# rpi_shield.net
KiCad netlist of a schematic drawn in Altium Designer
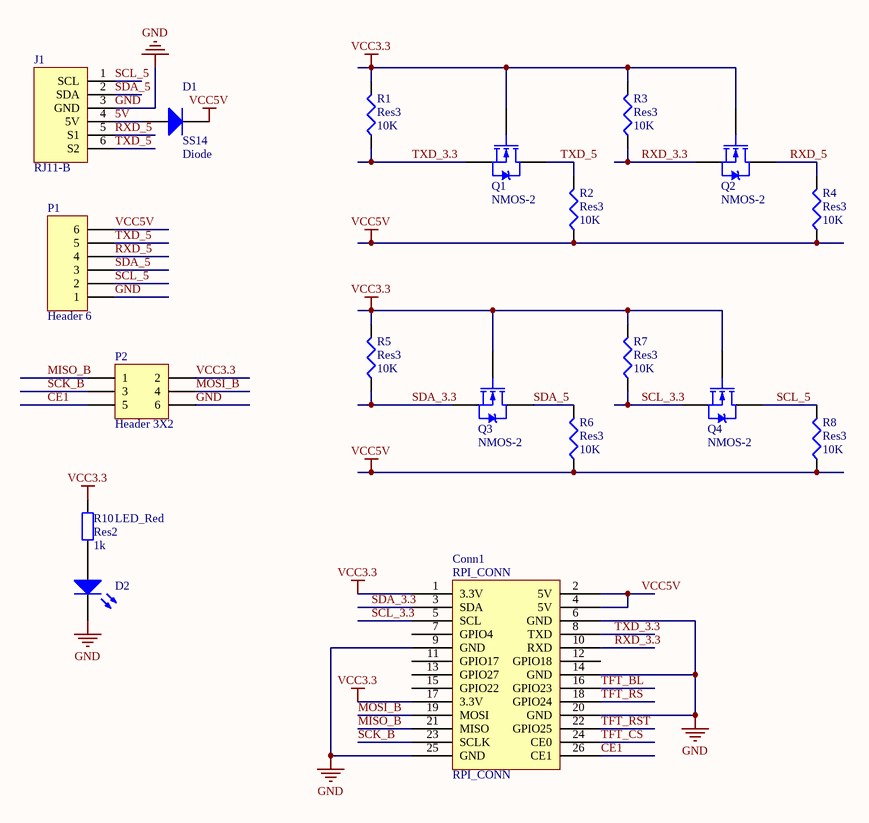
[diagram p0: rpi_shield.SchDoc]

(export (version "E")
  (design (tool "Eeschema 10.0.6"))
  (components
    (comp (ref "Conn1") (value "RPI_CONN") (footprint "HDR2X13") (libsource (lib "rpi") (part "RPI_CONN")))
    (comp (ref "D1")
      (value "Diode")
      (footprint "DO-214")
      (description "Default Diode")
      (fields (field (name "ALTIUM_VALUE") "SS14") (field (name "PUBLISHER") "Altium Limited"))
      (libsource (lib "Miscellaneous Devices") (part "Diode"))
    )
    (comp (ref "D2")
      (value "LED_Red")
      (footprint "D0603_B")
      (description "Typical BLUE SiC LED")
      (fields (field (name "PUBLISHER") "Altium Limited"))
      (libsource (lib "Miscellaneous Devices") (part "LED3"))
    )
    (comp (ref "J1") (value "RJ11-B") (footprint "PCB-606") (libsource (lib "Mylib") (part "RJ11-B")))
    (comp (ref "P1")
      (value "Header 6")
      (footprint "HDR1X6")
      (description "Header, 6-Pin")
      (fields (field (name "PUBLISHER") "Altium Limited"))
      (libsource (lib "Miscellaneous Connectors") (part "Header 6"))
    )
    (comp (ref "P2")
      (value "Header 3X2")
      (footprint "HDR2X3")
      (description "Header, 3-Pin, Dual row")
      (fields (field (name "PUBLISHER") "Altium Limited"))
      (libsource (lib "Miscellaneous Connectors") (part "Header 3X2"))
    )
    (comp (ref "Q1")
      (value "NMOS-2")
      (footprint "SOT-23-3")
      (description "N-Channel Power MOSFET")
      (fields (field (name "PUBLISHER") "Altium Limited"))
      (libsource (lib "Miscellaneous Devices") (part "NMOS-2"))
    )
    (comp (ref "Q2")
      (value "NMOS-2")
      (footprint "SOT-23-3")
      (description "N-Channel Power MOSFET")
      (fields (field (name "PUBLISHER") "Altium Limited"))
      (libsource (lib "Miscellaneous Devices") (part "NMOS-2"))
    )
    (comp (ref "Q3")
      (value "NMOS-2")
      (footprint "SOT-23-3")
      (description "N-Channel Power MOSFET")
      (fields (field (name "PUBLISHER") "Altium Limited"))
      (libsource (lib "Miscellaneous Devices") (part "NMOS-2"))
    )
    (comp (ref "Q4")
      (value "NMOS-2")
      (footprint "SOT-23-3")
      (description "N-Channel Power MOSFET")
      (fields (field (name "PUBLISHER") "Altium Limited"))
      (libsource (lib "Miscellaneous Devices") (part "NMOS-2"))
    )
    (comp (ref "R1")
      (value "Res3")
      (footprint "J1-0603")
      (description "Resistor")
      (fields (field (name "ALTIUM_VALUE") "10K") (field (name "PUBLISHER") "Altium Limited"))
      (libsource (lib "Miscellaneous Devices") (part "Res3"))
    )
    (comp (ref "R2")
      (value "Res3")
      (footprint "J1-0603")
      (description "Resistor")
      (fields (field (name "ALTIUM_VALUE") "10K") (field (name "PUBLISHER") "Altium Limited"))
      (libsource (lib "Miscellaneous Devices") (part "Res3"))
    )
    (comp (ref "R3")
      (value "Res3")
      (footprint "J1-0603")
      (description "Resistor")
      (fields (field (name "ALTIUM_VALUE") "10K") (field (name "PUBLISHER") "Altium Limited"))
      (libsource (lib "Miscellaneous Devices") (part "Res3"))
    )
    (comp (ref "R4")
      (value "Res3")
      (footprint "J1-0603")
      (description "Resistor")
      (fields (field (name "ALTIUM_VALUE") "10K") (field (name "PUBLISHER") "Altium Limited"))
      (libsource (lib "Miscellaneous Devices") (part "Res3"))
    )
    (comp (ref "R5")
      (value "Res3")
      (footprint "J1-0603")
      (description "Resistor")
      (fields (field (name "ALTIUM_VALUE") "10K") (field (name "PUBLISHER") "Altium Limited"))
      (libsource (lib "Miscellaneous Devices") (part "Res3"))
    )
    (comp (ref "R6")
      (value "Res3")
      (footprint "J1-0603")
      (description "Resistor")
      (fields (field (name "ALTIUM_VALUE") "10K") (field (name "PUBLISHER") "Altium Limited"))
      (libsource (lib "Miscellaneous Devices") (part "Res3"))
    )
    (comp (ref "R7")
      (value "Res3")
      (footprint "J1-0603")
      (description "Resistor")
      (fields (field (name "ALTIUM_VALUE") "10K") (field (name "PUBLISHER") "Altium Limited"))
      (libsource (lib "Miscellaneous Devices") (part "Res3"))
    )
    (comp (ref "R8")
      (value "Res3")
      (footprint "J1-0603")
      (description "Resistor")
      (fields (field (name "ALTIUM_VALUE") "10K") (field (name "PUBLISHER") "Altium Limited"))
      (libsource (lib "Miscellaneous Devices") (part "Res3"))
    )
    (comp (ref "R10")
      (value "Res2")
      (footprint "R0603")
      (description "Resistor")
      (fields (field (name "ALTIUM_VALUE") "1k") (field (name "PUBLISHER") "Altium Limited"))
      (libsource (lib "Miscellaneous Devices") (part "Res2"))
    )
  )
  (nets
    (net (code "1") (name "/5V") (class "Default")
      (node (ref "D1") (pin "1") (pinfunction "A_1") (pintype "passive"))
      (node (ref "J1") (pin "4") (pinfunction "5V_4") (pintype "passive"))
    )
    (net (code "2") (name "/CE1") (class "Default")
      (node (ref "Conn1") (pin "26") (pinfunction "CE1_26") (pintype "passive"))
      (node (ref "P2") (pin "5") (pinfunction "5_5") (pintype "passive"))
    )
    (net (code "3") (name "/MISO_B") (class "Default")
      (node (ref "Conn1") (pin "21") (pinfunction "MISO_21") (pintype "passive"))
      (node (ref "P2") (pin "1") (pinfunction "1_1") (pintype "passive"))
    )
    (net (code "4") (name "/MOSI_B") (class "Default")
      (node (ref "Conn1") (pin "19") (pinfunction "MOSI_19") (pintype "passive"))
      (node (ref "P2") (pin "4") (pinfunction "4_4") (pintype "passive"))
    )
    (net (code "5") (name "/RXD_3.3") (class "Default")
      (node (ref "Conn1") (pin "10") (pinfunction "RXD_10") (pintype "passive"))
      (node (ref "Q2") (pin "3") (pinfunction "S_3") (pintype "passive"))
      (node (ref "R3") (pin "1") (pinfunction "1_1") (pintype "passive"))
    )
    (net (code "6") (name "/RXD_5") (class "Default")
      (node (ref "J1") (pin "5") (pinfunction "S1_5") (pintype "passive"))
      (node (ref "P1") (pin "4") (pinfunction "4_4") (pintype "passive"))
      (node (ref "Q2") (pin "2") (pinfunction "D_2") (pintype "passive"))
      (node (ref "R4") (pin "2") (pinfunction "2_2") (pintype "passive"))
    )
    (net (code "7") (name "/SCK_B") (class "Default")
      (node (ref "Conn1") (pin "23") (pinfunction "SCLK_23") (pintype "passive"))
      (node (ref "P2") (pin "3") (pinfunction "3_3") (pintype "passive"))
    )
    (net (code "8") (name "/SCL_3.3") (class "Default")
      (node (ref "Conn1") (pin "5") (pinfunction "SCL_5") (pintype "passive"))
      (node (ref "Q4") (pin "3") (pinfunction "S_3") (pintype "passive"))
      (node (ref "R7") (pin "1") (pinfunction "1_1") (pintype "passive"))
    )
    (net (code "9") (name "/SCL_5") (class "Default")
      (node (ref "J1") (pin "1") (pinfunction "SCL_1") (pintype "passive"))
      (node (ref "P1") (pin "2") (pinfunction "2_2") (pintype "passive"))
      (node (ref "Q4") (pin "2") (pinfunction "D_2") (pintype "passive"))
      (node (ref "R8") (pin "2") (pinfunction "2_2") (pintype "passive"))
    )
    (net (code "10") (name "/SDA_3.3") (class "Default")
      (node (ref "Conn1") (pin "3") (pinfunction "SDA_3") (pintype "passive"))
      (node (ref "Q3") (pin "3") (pinfunction "S_3") (pintype "passive"))
      (node (ref "R5") (pin "1") (pinfunction "1_1") (pintype "passive"))
    )
    (net (code "11") (name "/SDA_5") (class "Default")
      (node (ref "J1") (pin "2") (pinfunction "SDA_2") (pintype "passive"))
      (node (ref "P1") (pin "3") (pinfunction "3_3") (pintype "passive"))
      (node (ref "Q3") (pin "2") (pinfunction "D_2") (pintype "passive"))
      (node (ref "R6") (pin "2") (pinfunction "2_2") (pintype "passive"))
    )
    (net (code "12") (name "/TFT_BL") (class "Default")
      (node (ref "Conn1") (pin "16") (pinfunction "GPIO23_16") (pintype "passive"))
    )
    (net (code "13") (name "/TFT_CS") (class "Default")
      (node (ref "Conn1") (pin "24") (pinfunction "CE0_24") (pintype "passive"))
    )
    (net (code "14") (name "/TFT_RS") (class "Default")
      (node (ref "Conn1") (pin "18") (pinfunction "GPIO24_18") (pintype "passive"))
    )
    (net (code "15") (name "/TFT_RST") (class "Default")
      (node (ref "Conn1") (pin "22") (pinfunction "GPIO25_22") (pintype "passive"))
    )
    (net (code "16") (name "/TXD_3.3") (class "Default")
      (node (ref "Conn1") (pin "8") (pinfunction "TXD_8") (pintype "passive"))
      (node (ref "Q1") (pin "3") (pinfunction "S_3") (pintype "passive"))
      (node (ref "R1") (pin "1") (pinfunction "1_1") (pintype "passive"))
    )
    (net (code "17") (name "/TXD_5") (class "Default")
      (node (ref "J1") (pin "6") (pinfunction "S2_6") (pintype "passive"))
      (node (ref "P1") (pin "5") (pinfunction "5_5") (pintype "passive"))
      (node (ref "Q1") (pin "2") (pinfunction "D_2") (pintype "passive"))
      (node (ref "R2") (pin "2") (pinfunction "2_2") (pintype "passive"))
    )
    (net (code "18") (name "GND") (class "Default")
      (node (ref "Conn1") (pin "14") (pinfunction "GND_14") (pintype "passive"))
      (node (ref "Conn1") (pin "20") (pinfunction "GND_20") (pintype "passive"))
      (node (ref "Conn1") (pin "25") (pinfunction "GND_25") (pintype "passive"))
      (node (ref "Conn1") (pin "6") (pinfunction "GND_6") (pintype "passive"))
      (node (ref "Conn1") (pin "9") (pinfunction "GND_9") (pintype "passive"))
      (node (ref "D2") (pin "2") (pinfunction "K_2") (pintype "passive"))
      (node (ref "J1") (pin "3") (pinfunction "GND_3") (pintype "passive"))
      (node (ref "P1") (pin "1") (pinfunction "1_1") (pintype "passive"))
      (node (ref "P2") (pin "6") (pinfunction "6_6") (pintype "passive"))
    )
    (net (code "19") (name "Net-(D2-A)") (class "Default")
      (node (ref "D2") (pin "1") (pinfunction "A_1") (pintype "passive"))
      (node (ref "R10") (pin "2") (pinfunction "2_2") (pintype "passive"))
    )
    (net (code "20") (name "VCC3.3") (class "Default")
      (node (ref "Conn1") (pin "1") (pinfunction "3.3V_1") (pintype "passive"))
      (node (ref "Conn1") (pin "17") (pinfunction "3.3V_17") (pintype "passive"))
      (node (ref "P2") (pin "2") (pinfunction "2_2") (pintype "passive"))
      (node (ref "Q1") (pin "1") (pinfunction "G_1") (pintype "passive"))
      (node (ref "Q2") (pin "1") (pinfunction "G_1") (pintype "passive"))
      (node (ref "Q3") (pin "1") (pinfunction "G_1") (pintype "passive"))
      (node (ref "Q4") (pin "1") (pinfunction "G_1") (pintype "passive"))
      (node (ref "R1") (pin "2") (pinfunction "2_2") (pintype "passive"))
      (node (ref "R10") (pin "1") (pinfunction "1_1") (pintype "passive"))
      (node (ref "R3") (pin "2") (pinfunction "2_2") (pintype "passive"))
      (node (ref "R5") (pin "2") (pinfunction "2_2") (pintype "passive"))
      (node (ref "R7") (pin "2") (pinfunction "2_2") (pintype "passive"))
    )
    (net (code "21") (name "VCC5V") (class "Default")
      (node (ref "Conn1") (pin "2") (pinfunction "5V_2") (pintype "passive"))
      (node (ref "Conn1") (pin "4") (pinfunction "5V_4") (pintype "passive"))
      (node (ref "D1") (pin "2") (pinfunction "K_2") (pintype "passive"))
      (node (ref "P1") (pin "6") (pinfunction "6_6") (pintype "passive"))
      (node (ref "R2") (pin "1") (pinfunction "1_1") (pintype "passive"))
      (node (ref "R4") (pin "1") (pinfunction "1_1") (pintype "passive"))
      (node (ref "R6") (pin "1") (pinfunction "1_1") (pintype "passive"))
      (node (ref "R8") (pin "1") (pinfunction "1_1") (pintype "passive"))
    )
    (net (code "22") (name "unconnected-(Conn1-GPIO4-Pad7)") (class "Default")
      (node (ref "Conn1") (pin "7") (pinfunction "GPIO4_7") (pintype "passive"))
    )
    (net (code "23") (name "unconnected-(Conn1-GPIO17-Pad11)") (class "Default")
      (node (ref "Conn1") (pin "11") (pinfunction "GPIO17_11") (pintype "passive"))
    )
    (net (code "24") (name "unconnected-(Conn1-GPIO18-Pad12)") (class "Default")
      (node (ref "Conn1") (pin "12") (pinfunction "GPIO18_12") (pintype "passive"))
    )
    (net (code "25") (name "unconnected-(Conn1-GPIO22-Pad15)") (class "Default")
      (node (ref "Conn1") (pin "15") (pinfunction "GPIO22_15") (pintype "passive"))
    )
    (net (code "26") (name "unconnected-(Conn1-GPIO27-Pad13)") (class "Default")
      (node (ref "Conn1") (pin "13") (pinfunction "GPIO27_13") (pintype "passive"))
    )
  )
)
